# ToneReal_Adapter_EE.net
KiCad netlist of a schematic drawn in Altium Designer
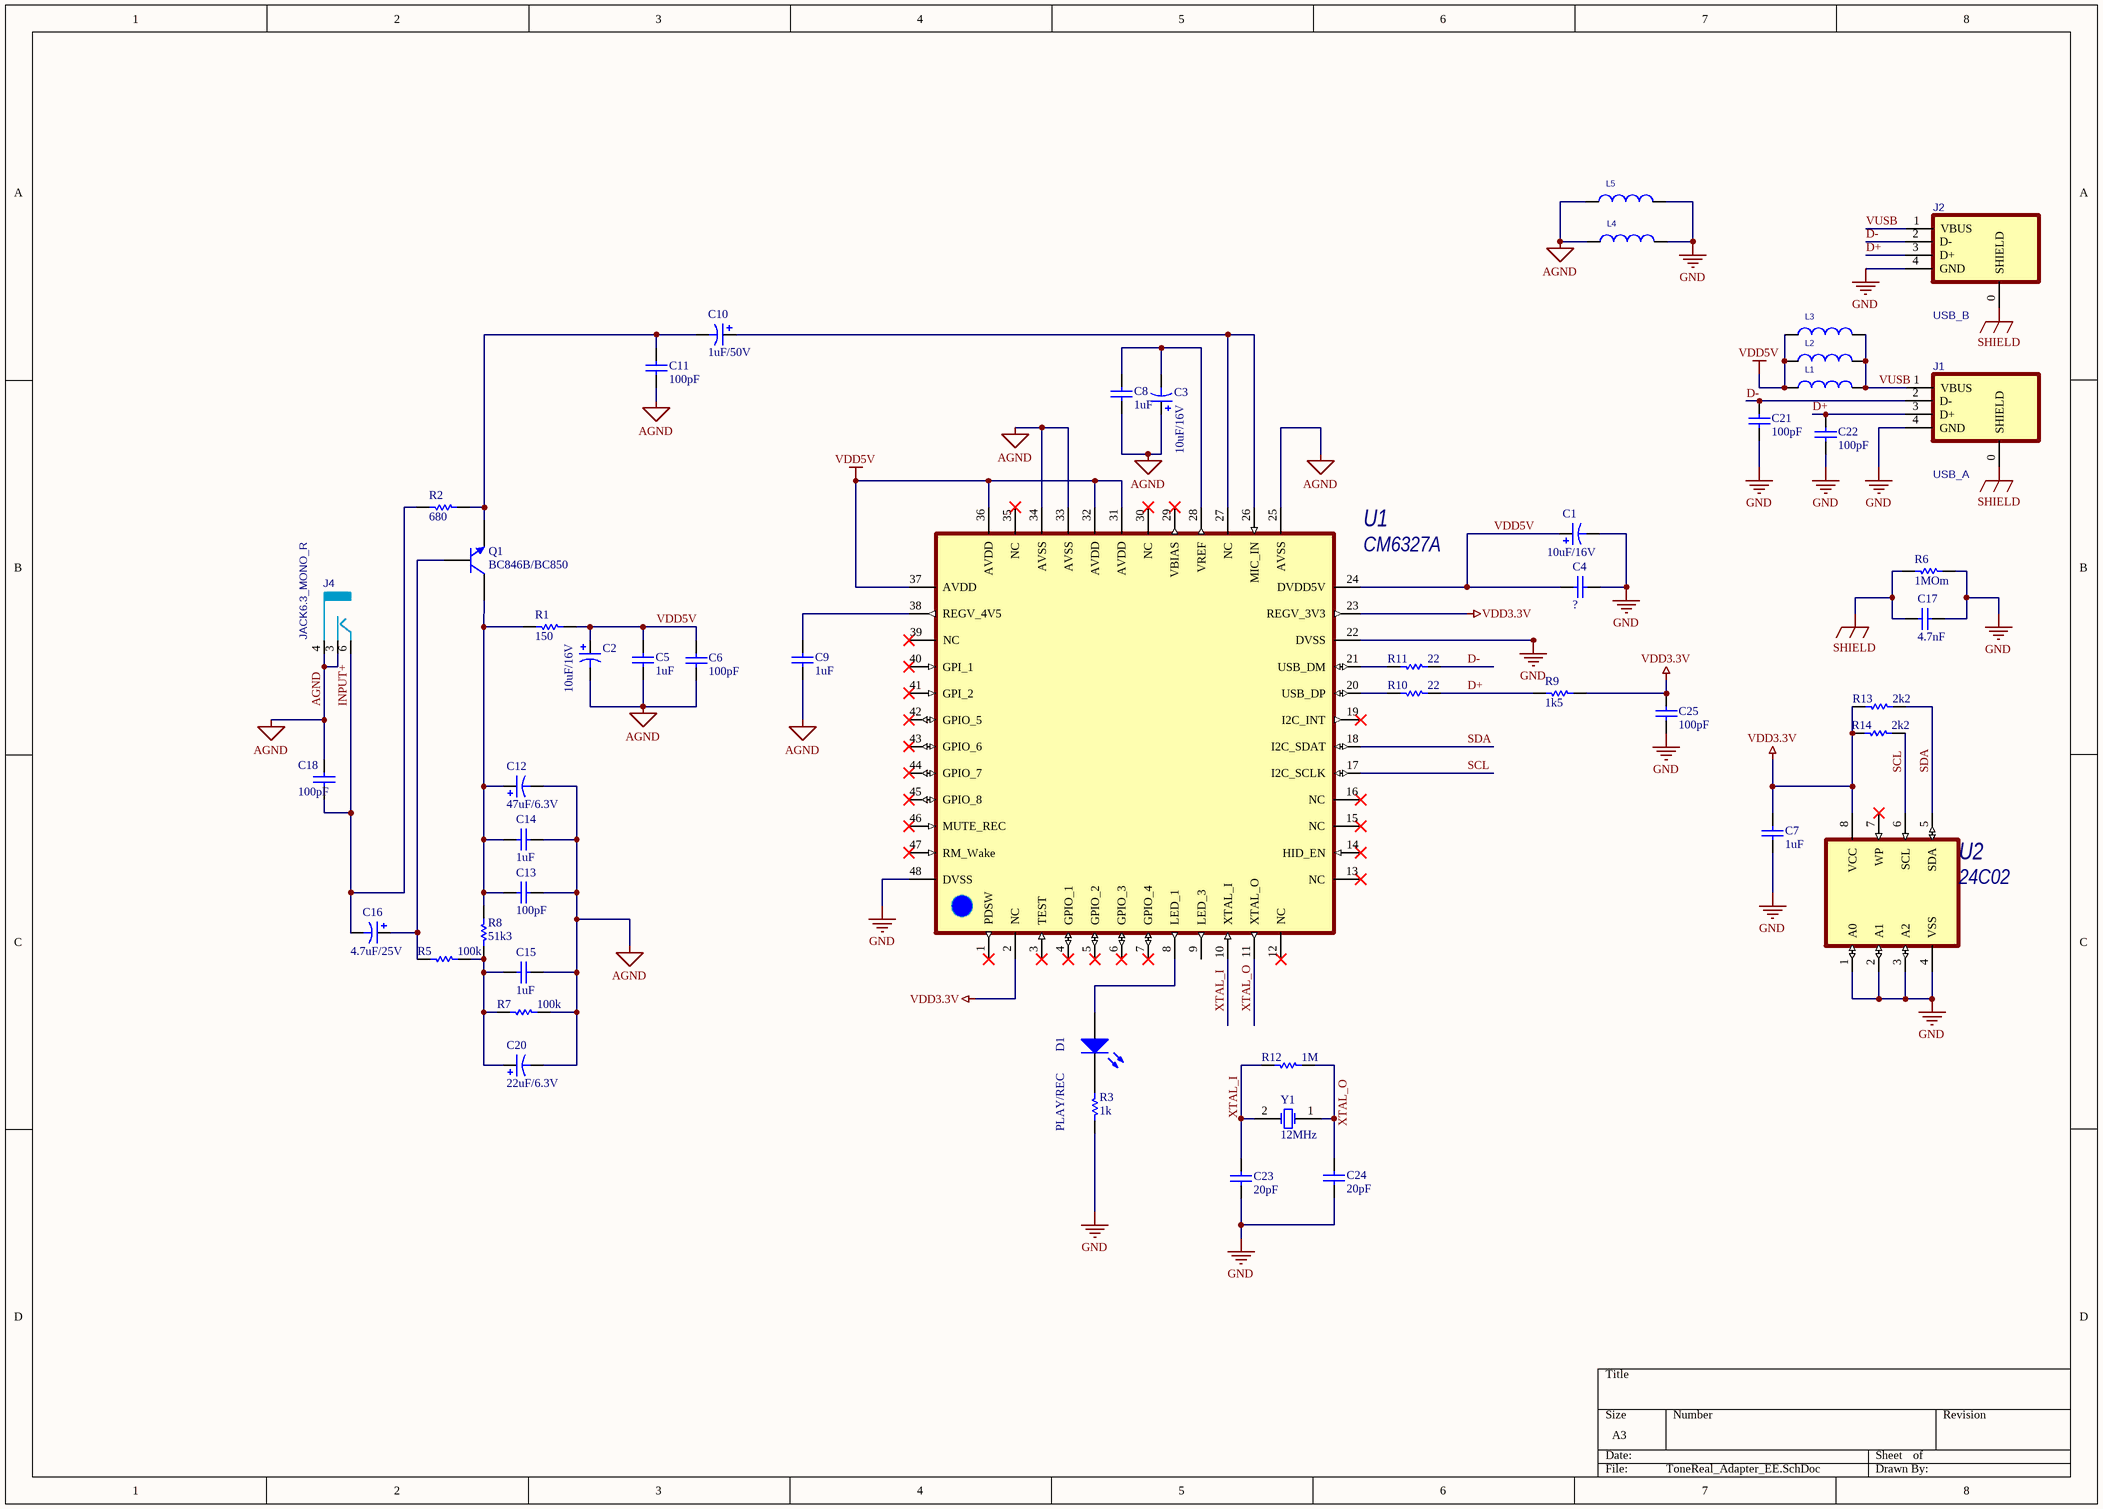
[diagram p0: ToneReal_Adapter_EE.SchDoc]

(export (version "E")
  (design (tool "Eeschema 10.0.6"))
  (components
    (comp (ref "C1")
      (value "10uF/16V")
      (footprint "TECAP SMD_B (IPC-3528)")
      (description "Polarized Capacitor (Surface Mount)")
      (fields (field (name "PUBLISHER") "Altium Limited"))
      (libsource (lib "Miscellaneous Devices") (part "Cap Pol3"))
    )
    (comp (ref "C2")
      (value "10uF/16V")
      (footprint "TECAP SMD_B (IPC-3528)")
      (description "Polarized Capacitor (Surface Mount)")
      (fields (field (name "PUBLISHER") "Altium Limited"))
      (libsource (lib "") (part "Cap Pol3_1"))
    )
    (comp (ref "C3")
      (value "10uF/16V")
      (footprint "TECAP SMD_B (IPC-3528)")
      (description "Polarized Capacitor (Surface Mount)")
      (fields (field (name "PUBLISHER") "Altium Limited"))
      (libsource (lib "") (part "Cap Pol3_1"))
    )
    (comp (ref "C4")
      (value "?")
      (footprint "CERCAP SMD0603L (IPC1608L)")
      (description "Capacitor (Semiconductor SIM Model)")
      (fields (field (name "PUBLISHER") "Altium Limited"))
      (libsource (lib "Miscellaneous Devices") (part "Cap Semi"))
    )
    (comp (ref "C5")
      (value "1uF")
      (footprint "CERCAP SMD0603L (IPC1608L)")
      (description "Capacitor (Semiconductor SIM Model)")
      (fields (field (name "PUBLISHER") "Altium Limited"))
      (libsource (lib "Miscellaneous Devices") (part "Cap Semi"))
    )
    (comp (ref "C6")
      (value "100pF")
      (footprint "CERCAP SMD0603L (IPC1608L)")
      (description "Capacitor (Semiconductor SIM Model)")
      (fields (field (name "PUBLISHER") "Altium Limited"))
      (libsource (lib "Miscellaneous Devices") (part "Cap Semi"))
    )
    (comp (ref "C7")
      (value "1uF")
      (footprint "CERCAP SMD0603L (IPC1608L)")
      (description "Capacitor (Semiconductor SIM Model)")
      (fields (field (name "PUBLISHER") "Altium Limited"))
      (libsource (lib "Miscellaneous Devices") (part "Cap Semi"))
    )
    (comp (ref "C8")
      (value "1uF")
      (footprint "CERCAP SMD0603L (IPC1608L)")
      (description "Capacitor (Semiconductor SIM Model)")
      (fields (field (name "PUBLISHER") "Altium Limited"))
      (libsource (lib "Miscellaneous Devices") (part "Cap Semi"))
    )
    (comp (ref "C9")
      (value "1uF")
      (footprint "CERCAP SMD0603L (IPC1608L)")
      (description "Capacitor (Semiconductor SIM Model)")
      (fields (field (name "PUBLISHER") "Altium Limited"))
      (libsource (lib "Miscellaneous Devices") (part "Cap Semi"))
    )
    (comp (ref "C10")
      (value "1uF/50V")
      (footprint "ECAP SMD KVE 5.0x5.3")
      (description "Polarized Capacitor (Surface Mount)")
      (fields (field (name "PUBLISHER") "Altium Limited"))
      (libsource (lib "Miscellaneous Devices") (part "Cap Pol3"))
    )
    (comp (ref "C11")
      (value "100pF")
      (footprint "CERCAP SMD0603L (IPC1608L)")
      (description "Capacitor (Semiconductor SIM Model)")
      (fields (field (name "PUBLISHER") "Altium Limited"))
      (libsource (lib "Miscellaneous Devices") (part "Cap Semi"))
    )
    (comp (ref "C12")
      (value "47uF/6.3V")
      (footprint "ECAP SMD KVE 5.0x5.3")
      (description "Polarized Capacitor (Surface Mount)")
      (fields (field (name "PUBLISHER") "Altium Limited"))
      (libsource (lib "Miscellaneous Devices") (part "Cap Pol3"))
    )
    (comp (ref "C13")
      (value "100pF")
      (footprint "CERCAP SMD0603L (IPC1608L)")
      (description "Capacitor (Semiconductor SIM Model)")
      (fields (field (name "PUBLISHER") "Altium Limited"))
      (libsource (lib "Miscellaneous Devices") (part "Cap Semi"))
    )
    (comp (ref "C14")
      (value "1uF")
      (footprint "CERCAP SMD0603L (IPC1608L)")
      (description "Capacitor (Semiconductor SIM Model)")
      (fields (field (name "PUBLISHER") "Altium Limited"))
      (libsource (lib "Miscellaneous Devices") (part "Cap Semi"))
    )
    (comp (ref "C15")
      (value "1uF")
      (footprint "CERCAP SMD0603L (IPC1608L)")
      (description "Capacitor (Semiconductor SIM Model)")
      (fields (field (name "PUBLISHER") "Altium Limited"))
      (libsource (lib "Miscellaneous Devices") (part "Cap Semi"))
    )
    (comp (ref "C16")
      (value "4.7uF/25V")
      (footprint "ECAP SMD KVE 5.0x5.3")
      (description "Polarized Capacitor (Surface Mount)")
      (fields (field (name "PUBLISHER") "Altium Limited"))
      (libsource (lib "Miscellaneous Devices") (part "Cap Pol3"))
    )
    (comp (ref "C17")
      (value "4.7nF")
      (footprint "CERCAP SMD0603L (IPC1608L)")
      (description "Capacitor (Semiconductor SIM Model)")
      (fields (field (name "PUBLISHER") "Altium Limited"))
      (libsource (lib "Miscellaneous Devices") (part "Cap Semi"))
    )
    (comp (ref "C18")
      (value "100pF")
      (footprint "CERCAP SMD0603L (IPC1608L)")
      (description "Capacitor (Semiconductor SIM Model)")
      (fields (field (name "PUBLISHER") "Altium Limited"))
      (libsource (lib "Miscellaneous Devices") (part "Cap Semi"))
    )
    (comp (ref "C20")
      (value "22uF/6.3V")
      (footprint "ECAP SMD KVE 5.0x5.3")
      (description "Polarized Capacitor (Surface Mount)")
      (fields (field (name "PUBLISHER") "Altium Limited"))
      (libsource (lib "Miscellaneous Devices") (part "Cap Pol3"))
    )
    (comp (ref "C21")
      (value "100pF")
      (footprint "CERCAP SMD0603L (IPC1608L)")
      (description "Capacitor (Semiconductor SIM Model)")
      (fields (field (name "PUBLISHER") "Altium Limited"))
      (libsource (lib "Miscellaneous Devices") (part "Cap Semi"))
    )
    (comp (ref "C22")
      (value "100pF")
      (footprint "CERCAP SMD0603L (IPC1608L)")
      (description "Capacitor (Semiconductor SIM Model)")
      (fields (field (name "PUBLISHER") "Altium Limited"))
      (libsource (lib "Miscellaneous Devices") (part "Cap Semi"))
    )
    (comp (ref "C23")
      (value "20pF")
      (footprint "CERCAP SMD0603L (IPC1608L)")
      (description "Capacitor (Semiconductor SIM Model)")
      (fields (field (name "PUBLISHER") "Altium Limited"))
      (libsource (lib "Miscellaneous Devices") (part "Cap Semi"))
    )
    (comp (ref "C24")
      (value "20pF")
      (footprint "CERCAP SMD0603L (IPC1608L)")
      (description "Capacitor (Semiconductor SIM Model)")
      (fields (field (name "PUBLISHER") "Altium Limited"))
      (libsource (lib "Miscellaneous Devices") (part "Cap Semi"))
    )
    (comp (ref "C25")
      (value "100pF")
      (footprint "CERCAP SMD0603L (IPC1608L)")
      (description "Capacitor (Semiconductor SIM Model)")
      (fields (field (name "PUBLISHER") "Altium Limited"))
      (libsource (lib "Miscellaneous Devices") (part "Cap Semi"))
    )
    (comp (ref "D1")
      (value "PLAY/REC")
      (footprint "SMDLED_0805")
      (description "Typical INFRARED GaAs LED")
      (fields (field (name "PUBLISHER") "Altium Limited"))
      (libsource (lib "Miscellaneous Devices") (part "LED0"))
    )
    (comp (ref "J1")
      (value "USB_A")
      (footprint "USBA_1PLAG")
      (fields
        (field (name "BOM_SUPPLIER PART") "C498173")
        (field (name "BOM_MANUFACTURER PART") "USB-B01")
        (field (name "CONTRIBUTOR") "LCSC")
      )
      (libsource (lib "ToneReal") (part "USB"))
    )
    (comp (ref "J2")
      (value "USB_B")
      (footprint "USB-B")
      (fields
        (field (name "BOM_SUPPLIER PART") "C498173")
        (field (name "BOM_MANUFACTURER PART") "USB-B01")
        (field (name "CONTRIBUTOR") "LCSC")
      )
      (libsource (lib "ToneReal") (part "USB"))
    )
    (comp (ref "J4")
      (value "JACK6.3_MONO_R")
      (footprint "JACK6.3")
      (description "6.3_jack_mono")
      (libsource (lib "ToneReal") (part "JACK6.3_MONO_R"))
    )
    (comp (ref "L1")
      (value "BLM21PG221SN1")
      (footprint "BLM21P (0805 size)")
      (libsource (lib "*") (part "INDUCT"))
    )
    (comp (ref "L2")
      (value "BLM21PG221SN1")
      (footprint "BLM21P (0805 size)")
      (libsource (lib "*") (part "INDUCT"))
    )
    (comp (ref "L3")
      (value "BLM21PG221SN1")
      (footprint "BLM21P (0805 size)")
      (libsource (lib "*") (part "INDUCT"))
    )
    (comp (ref "L4")
      (value "BLM21PG221SN1")
      (footprint "BLM21P (0805 size)")
      (libsource (lib "*") (part "INDUCT"))
    )
    (comp (ref "L5")
      (value "BLM21PG221SN1")
      (footprint "BLM21P (0805 size)")
      (libsource (lib "*") (part "INDUCT"))
    )
    (comp (ref "Q1")
      (value "BC846B/BC850")
      (footprint "SOT_23")
      (description "NPN Bipolar Transistor")
      (fields (field (name "COMPAUTHOR") "Kungurcev.K."))
      (libsource (lib "MySchLib") (part "BC846B"))
    )
    (comp (ref "R1")
      (value "150")
      (footprint "RES smd0603 (IPC-1608)")
      (description "Resistor")
      (fields (field (name "PUBLISHER") "Altium Limited"))
      (libsource (lib "Discret") (part "RES"))
    )
    (comp (ref "R2")
      (value "680")
      (footprint "RES smd0603 (IPC-1608)")
      (description "Resistor")
      (fields (field (name "PUBLISHER") "Altium Limited"))
      (libsource (lib "Discret") (part "RES"))
    )
    (comp (ref "R3")
      (value "1k")
      (footprint "RES smd0603 (IPC-1608)")
      (description "Resistor")
      (fields (field (name "PUBLISHER") "Altium Limited"))
      (libsource (lib "") (part "RES_1"))
    )
    (comp (ref "R5")
      (value "100k")
      (footprint "RES smd0603 (IPC-1608)")
      (description "Resistor")
      (fields (field (name "PUBLISHER") "Altium Limited"))
      (libsource (lib "Discret") (part "RES"))
    )
    (comp (ref "R6")
      (value "1MOm")
      (footprint "RES smd0603 (IPC-1608)")
      (description "Resistor")
      (fields (field (name "PUBLISHER") "Altium Limited"))
      (libsource (lib "Discret") (part "RES"))
    )
    (comp (ref "R7")
      (value "100k")
      (footprint "RES smd0603 (IPC-1608)")
      (description "Resistor")
      (fields (field (name "PUBLISHER") "Altium Limited"))
      (libsource (lib "Discret") (part "RES"))
    )
    (comp (ref "R8")
      (value "51k3")
      (footprint "RES smd0603 (IPC-1608)")
      (description "Resistor")
      (fields (field (name "PUBLISHER") "Altium Limited"))
      (libsource (lib "") (part "RES_1"))
    )
    (comp (ref "R9")
      (value "1k5")
      (footprint "RES smd0603 (IPC-1608)")
      (description "Resistor")
      (fields (field (name "PUBLISHER") "Altium Limited"))
      (libsource (lib "Discret") (part "RES"))
    )
    (comp (ref "R10")
      (value "22")
      (footprint "RES smd0603 (IPC-1608)")
      (description "Resistor")
      (fields (field (name "PUBLISHER") "Altium Limited"))
      (libsource (lib "Discret") (part "RES"))
    )
    (comp (ref "R11")
      (value "22")
      (footprint "RES smd0603 (IPC-1608)")
      (description "Resistor")
      (fields (field (name "PUBLISHER") "Altium Limited"))
      (libsource (lib "Discret") (part "RES"))
    )
    (comp (ref "R12")
      (value "1M")
      (footprint "RES smd0603 (IPC-1608)")
      (description "Resistor")
      (fields (field (name "PUBLISHER") "Altium Limited"))
      (libsource (lib "Discret") (part "RES"))
    )
    (comp (ref "R13")
      (value "2k2")
      (footprint "RES smd0603 (IPC-1608)")
      (description "Resistor")
      (fields (field (name "PUBLISHER") "Altium Limited"))
      (libsource (lib "Discret") (part "RES"))
    )
    (comp (ref "R14")
      (value "2k2")
      (footprint "RES smd0603 (IPC-1608)")
      (description "Resistor")
      (fields (field (name "PUBLISHER") "Altium Limited"))
      (libsource (lib "Discret") (part "RES"))
    )
    (comp (ref "U1")
      (value "CM6327A")
      (footprint "QFP50P900X900X160-48N")
      (description "CM6327")
      (libsource (lib "ToneReal") (part "CM6327_1"))
    )
    (comp (ref "U2") (value "24C02") (footprint "SOIC-8") (libsource (lib "ToneReal") (part "24C02")))
    (comp (ref "Y1")
      (value "12MHz")
      (footprint "HC-49/U3H  (KX-3H)")
      (description "Crystal Oscillator")
      (fields (field (name "PUBLISHER") "Altium Limited"))
      (libsource (lib "Clocks") (part "XTAL"))
    )
  )
  (nets
    (net (code "1") (name "/D+") (class "Default")
      (node (ref "C22") (pin "2") (pinfunction "2_2") (pintype "passive"))
      (node (ref "J1") (pin "3") (pinfunction "D+_3") (pintype "passive"))
      (node (ref "J2") (pin "3") (pinfunction "D+_3") (pintype "passive"))
      (node (ref "R10") (pin "2") (pinfunction "2_2") (pintype "passive"))
      (node (ref "R9") (pin "2") (pinfunction "2_2") (pintype "passive"))
    )
    (net (code "2") (name "/D-") (class "Default")
      (node (ref "C21") (pin "2") (pinfunction "2_2") (pintype "passive"))
      (node (ref "J1") (pin "2") (pinfunction "D-_2") (pintype "passive"))
      (node (ref "J2") (pin "2") (pinfunction "D-_2") (pintype "passive"))
      (node (ref "R11") (pin "2") (pinfunction "2_2") (pintype "passive"))
    )
    (net (code "3") (name "/INPUT+") (class "Default")
      (node (ref "C16") (pin "2") (pinfunction "2_2") (pintype "passive"))
      (node (ref "C18") (pin "1") (pinfunction "1_1") (pintype "passive"))
      (node (ref "J4") (pin "6") (pinfunction "R_CH_6") (pintype "passive"))
      (node (ref "R2") (pin "1") (pinfunction "1_1") (pintype "passive"))
    )
    (net (code "4") (name "/SCL") (class "Default")
      (node (ref "R14") (pin "2") (pinfunction "2_2") (pintype "passive"))
      (node (ref "U1") (pin "17") (pinfunction "I2C_SCLK_17") (pintype "bidirectional"))
      (node (ref "U2") (pin "6") (pinfunction "SCL_6") (pintype "input"))
    )
    (net (code "5") (name "/SDA") (class "Default")
      (node (ref "R13") (pin "2") (pinfunction "2_2") (pintype "passive"))
      (node (ref "U1") (pin "18") (pinfunction "I2C_SDAT_18") (pintype "bidirectional"))
      (node (ref "U2") (pin "5") (pinfunction "SDA_5") (pintype "bidirectional"))
    )
    (net (code "6") (name "/VUSB") (class "Default")
      (node (ref "J1") (pin "1") (pinfunction "VBUS_1") (pintype "passive"))
      (node (ref "J2") (pin "1") (pinfunction "VBUS_1") (pintype "passive"))
      (node (ref "L1") (pin "2") (pinfunction "2_2") (pintype "passive"))
      (node (ref "L2") (pin "2") (pinfunction "2_2") (pintype "passive"))
      (node (ref "L3") (pin "2") (pinfunction "2_2") (pintype "passive"))
    )
    (net (code "7") (name "/XTAL_I") (class "Default")
      (node (ref "C23") (pin "2") (pinfunction "2_2") (pintype "passive"))
      (node (ref "R12") (pin "1") (pinfunction "1_1") (pintype "passive"))
      (node (ref "U1") (pin "10") (pinfunction "XTAL_I_10") (pintype "input"))
      (node (ref "Y1") (pin "2") (pinfunction "OSC2_2") (pintype "passive"))
    )
    (net (code "8") (name "/XTAL_O") (class "Default")
      (node (ref "C24") (pin "2") (pinfunction "2_2") (pintype "passive"))
      (node (ref "R12") (pin "2") (pinfunction "2_2") (pintype "passive"))
      (node (ref "U1") (pin "11") (pinfunction "XTAL_O_11") (pintype "output"))
      (node (ref "Y1") (pin "1") (pinfunction "OSC1_1") (pintype "passive"))
    )
    (net (code "9") (name "AGND") (class "Default")
      (node (ref "C11") (pin "2") (pinfunction "2_2") (pintype "passive"))
      (node (ref "C12") (pin "2") (pinfunction "2_2") (pintype "passive"))
      (node (ref "C13") (pin "1") (pinfunction "1_1") (pintype "passive"))
      (node (ref "C14") (pin "1") (pinfunction "1_1") (pintype "passive"))
      (node (ref "C15") (pin "1") (pinfunction "1_1") (pintype "passive"))
      (node (ref "C18") (pin "2") (pinfunction "2_2") (pintype "passive"))
      (node (ref "C2") (pin "2") (pinfunction "2_2") (pintype "passive"))
      (node (ref "C20") (pin "2") (pinfunction "2_2") (pintype "passive"))
      (node (ref "C3") (pin "1") (pinfunction "1_1") (pintype "passive"))
      (node (ref "C5") (pin "2") (pinfunction "2_2") (pintype "passive"))
      (node (ref "C6") (pin "2") (pinfunction "2_2") (pintype "passive"))
      (node (ref "C8") (pin "2") (pinfunction "2_2") (pintype "passive"))
      (node (ref "C9") (pin "2") (pinfunction "2_2") (pintype "passive"))
      (node (ref "J4") (pin "3") (pinfunction "R_ch_closed_3") (pintype "passive"))
      (node (ref "J4") (pin "4") (pinfunction "GND_4") (pintype "passive"))
      (node (ref "L4") (pin "1") (pinfunction "1_1") (pintype "passive"))
      (node (ref "L5") (pin "1") (pinfunction "1_1") (pintype "passive"))
      (node (ref "R7") (pin "2") (pinfunction "2_2") (pintype "passive"))
      (node (ref "U1") (pin "25") (pinfunction "AVSS_25") (pintype "power_in"))
      (node (ref "U1") (pin "33") (pinfunction "AVSS_33") (pintype "power_in"))
      (node (ref "U1") (pin "34") (pinfunction "AVSS_34") (pintype "power_in"))
    )
    (net (code "10") (name "GND") (class "Default")
      (node (ref "C1") (pin "2") (pinfunction "2_2") (pintype "passive"))
      (node (ref "C17") (pin "2") (pinfunction "2_2") (pintype "passive"))
      (node (ref "C21") (pin "1") (pinfunction "1_1") (pintype "passive"))
      (node (ref "C22") (pin "1") (pinfunction "1_1") (pintype "passive"))
      (node (ref "C23") (pin "1") (pinfunction "1_1") (pintype "passive"))
      (node (ref "C24") (pin "1") (pinfunction "1_1") (pintype "passive"))
      (node (ref "C25") (pin "1") (pinfunction "1_1") (pintype "passive"))
      (node (ref "C4") (pin "1") (pinfunction "1_1") (pintype "passive"))
      (node (ref "C7") (pin "1") (pinfunction "1_1") (pintype "passive"))
      (node (ref "J1") (pin "4") (pinfunction "GND_4") (pintype "passive"))
      (node (ref "J2") (pin "4") (pinfunction "GND_4") (pintype "passive"))
      (node (ref "L4") (pin "2") (pinfunction "2_2") (pintype "passive"))
      (node (ref "L5") (pin "2") (pinfunction "2_2") (pintype "passive"))
      (node (ref "R3") (pin "2") (pinfunction "2_2") (pintype "passive"))
      (node (ref "R6") (pin "1") (pinfunction "1_1") (pintype "passive"))
      (node (ref "U1") (pin "22") (pinfunction "DVSS_22") (pintype "power_in"))
      (node (ref "U1") (pin "48") (pinfunction "DVSS_48") (pintype "power_in"))
      (node (ref "U2") (pin "1") (pinfunction "A0_1") (pintype "bidirectional"))
      (node (ref "U2") (pin "2") (pinfunction "A1_2") (pintype "bidirectional"))
      (node (ref "U2") (pin "3") (pinfunction "A2_3") (pintype "bidirectional"))
      (node (ref "U2") (pin "4") (pinfunction "VSS_4") (pintype "power_in"))
    )
    (net (code "11") (name "Net-(C15-Pad2)") (class "Default")
      (node (ref "C15") (pin "2") (pinfunction "2_2") (pintype "passive"))
      (node (ref "C20") (pin "1") (pinfunction "1_1") (pintype "passive"))
      (node (ref "R5") (pin "2") (pinfunction "2_2") (pintype "passive"))
      (node (ref "R7") (pin "1") (pinfunction "1_1") (pintype "passive"))
      (node (ref "R8") (pin "1") (pinfunction "1_1") (pintype "passive"))
    )
    (net (code "12") (name "Net-(D1-A)") (class "Default")
      (node (ref "D1") (pin "2") (pinfunction "A_2") (pintype "passive"))
      (node (ref "U1") (pin "8") (pinfunction "LED_1_8") (pintype "output"))
    )
    (net (code "13") (name "Net-(D1-K)") (class "Default")
      (node (ref "D1") (pin "1") (pinfunction "K_1") (pintype "passive"))
      (node (ref "R3") (pin "1") (pinfunction "1_1") (pintype "passive"))
    )
    (net (code "14") (name "Net-(Q1-B)") (class "Default")
      (node (ref "C16") (pin "1") (pinfunction "1_1") (pintype "passive"))
      (node (ref "Q1") (pin "1") (pinfunction "B_1") (pintype "passive"))
      (node (ref "R5") (pin "1") (pinfunction "1_1") (pintype "passive"))
    )
    (net (code "15") (name "Net-(Q1-C)") (class "Default")
      (node (ref "C12") (pin "1") (pinfunction "1_1") (pintype "passive"))
      (node (ref "C13") (pin "2") (pinfunction "2_2") (pintype "passive"))
      (node (ref "C14") (pin "2") (pinfunction "2_2") (pintype "passive"))
      (node (ref "Q1") (pin "3") (pinfunction "C_3") (pintype "passive"))
      (node (ref "R1") (pin "2") (pinfunction "2_2") (pintype "passive"))
      (node (ref "R8") (pin "2") (pinfunction "2_2") (pintype "passive"))
    )
    (net (code "16") (name "Net-(Q1-E)") (class "Default")
      (node (ref "C10") (pin "2") (pinfunction "2_2") (pintype "passive"))
      (node (ref "C11") (pin "1") (pinfunction "1_1") (pintype "passive"))
      (node (ref "Q1") (pin "2") (pinfunction "E_2") (pintype "passive"))
      (node (ref "R2") (pin "2") (pinfunction "2_2") (pintype "passive"))
    )
    (net (code "17") (name "Net-(U1-MIC_IN)") (class "Default")
      (node (ref "C10") (pin "1") (pinfunction "1_1") (pintype "passive"))
      (node (ref "U1") (pin "26") (pinfunction "MIC_IN_26") (pintype "input"))
      (node (ref "U1") (pin "27") (pinfunction "NC_27") (pintype "passive"))
    )
    (net (code "18") (name "Net-(U1-REGV_4V5)") (class "Default")
      (node (ref "C9") (pin "1") (pinfunction "1_1") (pintype "passive"))
      (node (ref "U1") (pin "38") (pinfunction "REGV_4V5_38") (pintype "output"))
    )
    (net (code "19") (name "Net-(U1-USB_DM)") (class "Default")
      (node (ref "R11") (pin "1") (pinfunction "1_1") (pintype "passive"))
      (node (ref "U1") (pin "21") (pinfunction "USB_DM_21") (pintype "bidirectional"))
    )
    (net (code "20") (name "Net-(U1-USB_DP)") (class "Default")
      (node (ref "R10") (pin "1") (pinfunction "1_1") (pintype "passive"))
      (node (ref "U1") (pin "20") (pinfunction "USB_DP_20") (pintype "bidirectional"))
    )
    (net (code "21") (name "Net-(U1-VREF)") (class "Default")
      (node (ref "C3") (pin "2") (pinfunction "2_2") (pintype "passive"))
      (node (ref "C8") (pin "1") (pinfunction "1_1") (pintype "passive"))
      (node (ref "U1") (pin "28") (pinfunction "VREF_28") (pintype "output"))
    )
    (net (code "22") (name "SHIELD") (class "Default")
      (node (ref "C17") (pin "1") (pinfunction "1_1") (pintype "passive"))
      (node (ref "J1") (pin "0") (pinfunction "SHIELD_0") (pintype "passive"))
      (node (ref "J2") (pin "0") (pinfunction "SHIELD_0") (pintype "passive"))
      (node (ref "R6") (pin "2") (pinfunction "2_2") (pintype "passive"))
    )
    (net (code "23") (name "VDD3.3V") (class "Default")
      (node (ref "C25") (pin "2") (pinfunction "2_2") (pintype "passive"))
      (node (ref "C7") (pin "2") (pinfunction "2_2") (pintype "passive"))
      (node (ref "R13") (pin "1") (pinfunction "1_1") (pintype "passive"))
      (node (ref "R14") (pin "1") (pinfunction "1_1") (pintype "passive"))
      (node (ref "R9") (pin "1") (pinfunction "1_1") (pintype "passive"))
      (node (ref "U1") (pin "2") (pinfunction "NC_2") (pintype "passive"))
      (node (ref "U1") (pin "23") (pinfunction "REGV_3V3_23") (pintype "output"))
      (node (ref "U2") (pin "8") (pinfunction "VCC_8") (pintype "power_in"))
    )
    (net (code "24") (name "VDD5V") (class "Default")
      (node (ref "C1") (pin "1") (pinfunction "1_1") (pintype "passive"))
      (node (ref "C2") (pin "1") (pinfunction "1_1") (pintype "passive"))
      (node (ref "C4") (pin "2") (pinfunction "2_2") (pintype "passive"))
      (node (ref "C5") (pin "1") (pinfunction "1_1") (pintype "passive"))
      (node (ref "C6") (pin "1") (pinfunction "1_1") (pintype "passive"))
      (node (ref "L1") (pin "1") (pinfunction "1_1") (pintype "passive"))
      (node (ref "L2") (pin "1") (pinfunction "1_1") (pintype "passive"))
      (node (ref "L3") (pin "1") (pinfunction "1_1") (pintype "passive"))
      (node (ref "R1") (pin "1") (pinfunction "1_1") (pintype "passive"))
      (node (ref "U1") (pin "24") (pinfunction "DVDD5V_24") (pintype "power_in"))
      (node (ref "U1") (pin "31") (pinfunction "AVDD_31") (pintype "power_in"))
      (node (ref "U1") (pin "32") (pinfunction "AVDD_32") (pintype "power_in"))
      (node (ref "U1") (pin "36") (pinfunction "AVDD_36") (pintype "power_in"))
      (node (ref "U1") (pin "37") (pinfunction "AVDD_37") (pintype "power_in"))
    )
    (net (code "25") (name "unconnected-(U1-GPIO_1-Pad4)") (class "Default")
      (node (ref "U1") (pin "4") (pinfunction "GPIO_1_4") (pintype "bidirectional+no_connect"))
    )
    (net (code "26") (name "unconnected-(U1-GPIO_2-Pad5)") (class "Default")
      (node (ref "U1") (pin "5") (pinfunction "GPIO_2_5") (pintype "bidirectional+no_connect"))
    )
    (net (code "27") (name "unconnected-(U1-GPIO_3-Pad6)") (class "Default")
      (node (ref "U1") (pin "6") (pinfunction "GPIO_3_6") (pintype "bidirectional+no_connect"))
    )
    (net (code "28") (name "unconnected-(U1-GPIO_4-Pad7)") (class "Default")
      (node (ref "U1") (pin "7") (pinfunction "GPIO_4_7") (pintype "bidirectional+no_connect"))
    )
    (net (code "29") (name "unconnected-(U1-GPIO_5-Pad42)") (class "Default")
      (node (ref "U1") (pin "42") (pinfunction "GPIO_5_42") (pintype "bidirectional+no_connect"))
    )
    (net (code "30") (name "unconnected-(U1-GPIO_6-Pad43)") (class "Default")
      (node (ref "U1") (pin "43") (pinfunction "GPIO_6_43") (pintype "bidirectional+no_connect"))
    )
    (net (code "31") (name "unconnected-(U1-GPIO_7-Pad44)") (class "Default")
      (node (ref "U1") (pin "44") (pinfunction "GPIO_7_44") (pintype "bidirectional+no_connect"))
    )
    (net (code "32") (name "unconnected-(U1-GPIO_8-Pad45)") (class "Default")
      (node (ref "U1") (pin "45") (pinfunction "GPIO_8_45") (pintype "bidirectional+no_connect"))
    )
    (net (code "33") (name "unconnected-(U1-GPI_1-Pad40)") (class "Default")
      (node (ref "U1") (pin "40") (pinfunction "GPI_1_40") (pintype "input+no_connect"))
    )
    (net (code "34") (name "unconnected-(U1-GPI_2-Pad41)") (class "Default")
      (node (ref "U1") (pin "41") (pinfunction "GPI_2_41") (pintype "input+no_connect"))
    )
    (net (code "35") (name "unconnected-(U1-HID_EN-Pad14)") (class "Default")
      (node (ref "U1") (pin "14") (pinfunction "HID_EN_14") (pintype "input+no_connect"))
    )
    (net (code "36") (name "unconnected-(U1-I2C_INT-Pad19)") (class "Default")
      (node (ref "U1") (pin "19") (pinfunction "I2C_INT_19") (pintype "output+no_connect"))
    )
    (net (code "37") (name "unconnected-(U1-LED_3-Pad9)") (class "Default")
      (node (ref "U1") (pin "9") (pinfunction "LED_3_9") (pintype "output"))
    )
    (net (code "38") (name "unconnected-(U1-MUTE_REC-Pad46)") (class "Default")
      (node (ref "U1") (pin "46") (pinfunction "MUTE_REC_46") (pintype "input+no_connect"))
    )
    (net (code "39") (name "unconnected-(U1-NC-Pad12)") (class "Default")
      (node (ref "U1") (pin "12") (pinfunction "NC_12") (pintype "passive+no_connect"))
    )
    (net (code "40") (name "unconnected-(U1-NC-Pad13)") (class "Default")
      (node (ref "U1") (pin "13") (pinfunction "NC_13") (pintype "passive+no_connect"))
    )
    (net (code "41") (name "unconnected-(U1-NC-Pad15)") (class "Default")
      (node (ref "U1") (pin "15") (pinfunction "NC_15") (pintype "passive+no_connect"))
    )
    (net (code "42") (name "unconnected-(U1-NC-Pad16)") (class "Default")
      (node (ref "U1") (pin "16") (pinfunction "NC_16") (pintype "passive+no_connect"))
    )
    (net (code "43") (name "unconnected-(U1-NC-Pad30)") (class "Default")
      (node (ref "U1") (pin "30") (pinfunction "NC_30") (pintype "passive+no_connect"))
    )
    (net (code "44") (name "unconnected-(U1-NC-Pad35)") (class "Default")
      (node (ref "U1") (pin "35") (pinfunction "NC_35") (pintype "passive+no_connect"))
    )
    (net (code "45") (name "unconnected-(U1-NC-Pad39)") (class "Default")
      (node (ref "U1") (pin "39") (pinfunction "NC_39") (pintype "passive+no_connect"))
    )
    (net (code "46") (name "unconnected-(U1-PDSW-Pad1)") (class "Default")
      (node (ref "U1") (pin "1") (pinfunction "PDSW_1") (pintype "output+no_connect"))
    )
    (net (code "47") (name "unconnected-(U1-RM_Wake-Pad47)") (class "Default")
      (node (ref "U1") (pin "47") (pinfunction "RM_Wake_47") (pintype "input+no_connect"))
    )
    (net (code "48") (name "unconnected-(U1-TEST-Pad3)") (class "Default")
      (node (ref "U1") (pin "3") (pinfunction "TEST_3") (pintype "input+no_connect"))
    )
    (net (code "49") (name "unconnected-(U1-VBIAS-Pad29)") (class "Default")
      (node (ref "U1") (pin "29") (pinfunction "VBIAS_29") (pintype "output+no_connect"))
    )
    (net (code "50") (name "unconnected-(U2-WP-Pad7)") (class "Default")
      (node (ref "U2") (pin "7") (pinfunction "WP_7") (pintype "input+no_connect"))
    )
  )
)
